# connections.net
KiCad netlist of a schematic drawn in EAGLE
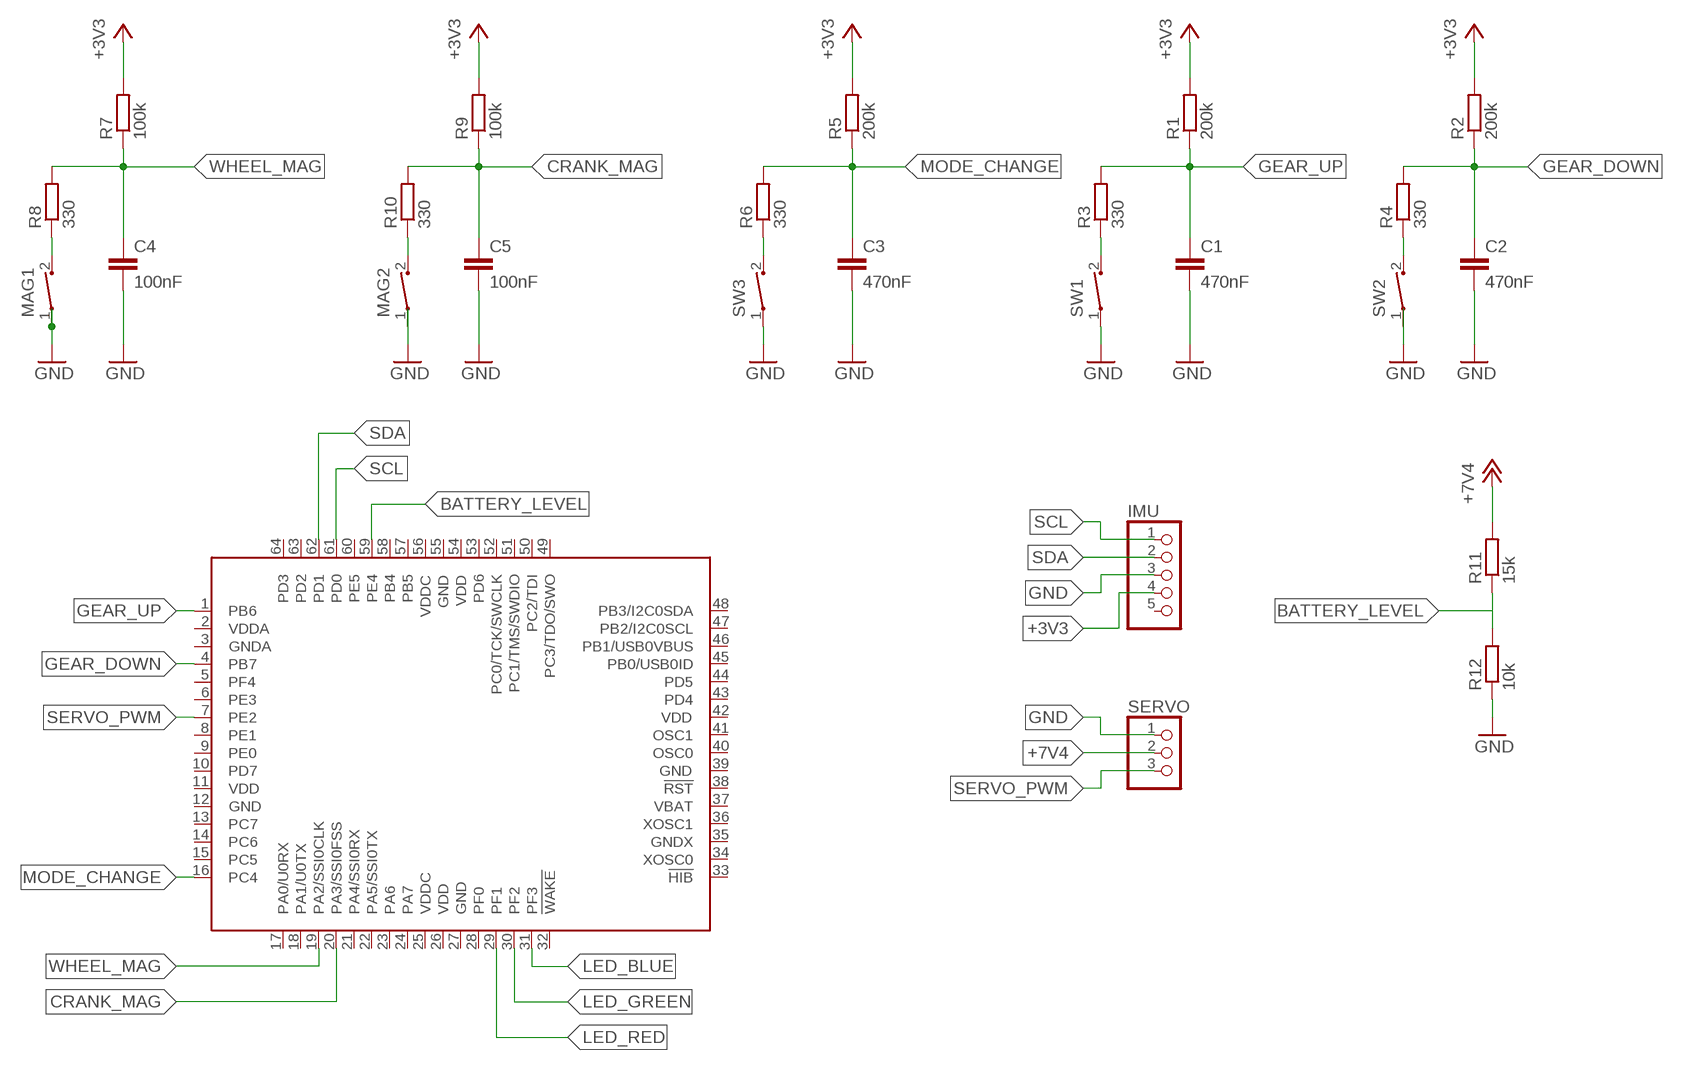
[diagram p0: schematic, sheet 1]

(export (version "E")
  (design (tool "Eeschema 10.0.6"))
  (components
    (comp (ref "C1")
      (value "470nF")
      (footprint "eagle-import:C2.5-3")
      (libsource (lib "eagle-import") (part "C2,5-3"))
    )
    (comp (ref "C2")
      (value "470nF")
      (footprint "eagle-import:C2.5-3")
      (libsource (lib "eagle-import") (part "C2,5-3"))
    )
    (comp (ref "C3")
      (value "470nF")
      (footprint "eagle-import:C2.5-3")
      (libsource (lib "eagle-import") (part "C2,5-3"))
    )
    (comp (ref "C4")
      (value "100nF")
      (footprint "eagle-import:C2.5-3")
      (libsource (lib "eagle-import") (part "C2,5-3"))
    )
    (comp (ref "C5")
      (value "100nF")
      (footprint "eagle-import:C2.5-3")
      (libsource (lib "eagle-import") (part "C2,5-3"))
    )
    (comp (ref "IC1")
      (value "TM4C123[7,G]XXPM")
      (footprint "eagle-import:PM_S-PQFP-G64")
      (libsource (lib "eagle-import") (part "TM4C123[7,G]XXPM"))
    )
    (comp (ref "IMU")
      (value "PINHD-1X5")
      (footprint "eagle-import:1X05")
      (libsource (lib "eagle-import") (part "PINHD-1X5"))
    )
    (comp (ref "MAG1")
      (value "CT10-XXXX-A2")
      (footprint "eagle-import:CT10-XXXX-A2")
      (libsource (lib "eagle-import") (part "CT10-XXXX-A2"))
    )
    (comp (ref "MAG2")
      (value "CT10-XXXX-A2")
      (footprint "eagle-import:CT10-XXXX-A2")
      (libsource (lib "eagle-import") (part "CT10-XXXX-A2"))
    )
    (comp (ref "R1")
      (value "200k")
      (footprint "eagle-import:0204_5")
      (libsource (lib "eagle-import") (part "R-EU_0204/5"))
    )
    (comp (ref "R2")
      (value "200k")
      (footprint "eagle-import:0204_5")
      (libsource (lib "eagle-import") (part "R-EU_0204/5"))
    )
    (comp (ref "R3")
      (value "330")
      (footprint "eagle-import:0204_5")
      (libsource (lib "eagle-import") (part "R-EU_0204/5"))
    )
    (comp (ref "R4")
      (value "330")
      (footprint "eagle-import:0204_5")
      (libsource (lib "eagle-import") (part "R-EU_0204/5"))
    )
    (comp (ref "R5")
      (value "200k")
      (footprint "eagle-import:0204_5")
      (libsource (lib "eagle-import") (part "R-EU_0204/5"))
    )
    (comp (ref "R6")
      (value "330")
      (footprint "eagle-import:0204_5")
      (libsource (lib "eagle-import") (part "R-EU_0204/5"))
    )
    (comp (ref "R7")
      (value "100k")
      (footprint "eagle-import:0204_5")
      (libsource (lib "eagle-import") (part "R-EU_0204/5"))
    )
    (comp (ref "R8")
      (value "330")
      (footprint "eagle-import:0204_5")
      (libsource (lib "eagle-import") (part "R-EU_0204/5"))
    )
    (comp (ref "R9")
      (value "100k")
      (footprint "eagle-import:0204_5")
      (libsource (lib "eagle-import") (part "R-EU_0204/5"))
    )
    (comp (ref "R10")
      (value "330")
      (footprint "eagle-import:0204_5")
      (libsource (lib "eagle-import") (part "R-EU_0204/5"))
    )
    (comp (ref "R11")
      (value "15k")
      (footprint "eagle-import:0204_5")
      (libsource (lib "eagle-import") (part "R-EU_0204/5"))
    )
    (comp (ref "R12")
      (value "10k")
      (footprint "eagle-import:0204_5")
      (libsource (lib "eagle-import") (part "R-EU_0204/5"))
    )
    (comp (ref "SERVO")
      (value "PINHD-1X3")
      (footprint "eagle-import:1X03")
      (libsource (lib "eagle-import") (part "PINHD-1X3"))
    )
    (comp (ref "SW1")
      (value "CT10-XXXX-A2")
      (footprint "eagle-import:CT10-XXXX-A2")
      (libsource (lib "eagle-import") (part "CT10-XXXX-A2"))
    )
    (comp (ref "SW2")
      (value "CT10-XXXX-A2")
      (footprint "eagle-import:CT10-XXXX-A2")
      (libsource (lib "eagle-import") (part "CT10-XXXX-A2"))
    )
    (comp (ref "SW3")
      (value "CT10-XXXX-A2")
      (footprint "eagle-import:CT10-XXXX-A2")
      (libsource (lib "eagle-import") (part "CT10-XXXX-A2"))
    )
  )
  (nets
    (net (code "1") (name "+3V3") (class "Default")
      (node (ref "IMU") (pin "4") (pinfunction "4_4") (pintype "passive"))
      (node (ref "R1") (pin "2") (pinfunction "2_2") (pintype "passive"))
      (node (ref "R2") (pin "2") (pinfunction "2_2") (pintype "passive"))
      (node (ref "R5") (pin "2") (pinfunction "2_2") (pintype "passive"))
      (node (ref "R7") (pin "2") (pinfunction "2_2") (pintype "passive"))
      (node (ref "R9") (pin "2") (pinfunction "2_2") (pintype "passive"))
    )
    (net (code "2") (name "+7V4") (class "Default")
      (node (ref "R11") (pin "2") (pinfunction "2_2") (pintype "passive"))
      (node (ref "SERVO") (pin "2") (pinfunction "2_2") (pintype "passive"))
    )
    (net (code "3") (name "BATTERY_LEVEL") (class "Default")
      (node (ref "IC1") (pin "59") (pinfunction "PE4_59") (pintype "bidirectional"))
      (node (ref "R11") (pin "1") (pinfunction "1_1") (pintype "passive"))
      (node (ref "R12") (pin "2") (pinfunction "2_2") (pintype "passive"))
    )
    (net (code "4") (name "CRANK_MAG") (class "Default")
      (node (ref "C5") (pin "1") (pinfunction "1_1") (pintype "passive"))
      (node (ref "IC1") (pin "20") (pinfunction "PA3/SSI0FSS_20") (pintype "bidirectional"))
      (node (ref "R10") (pin "2") (pinfunction "2_2") (pintype "passive"))
      (node (ref "R9") (pin "1") (pinfunction "1_1") (pintype "passive"))
    )
    (net (code "5") (name "GEAR_DOWN") (class "Default")
      (node (ref "C2") (pin "1") (pinfunction "1_1") (pintype "passive"))
      (node (ref "IC1") (pin "4") (pinfunction "PB7_4") (pintype "bidirectional"))
      (node (ref "R2") (pin "1") (pinfunction "1_1") (pintype "passive"))
      (node (ref "R4") (pin "2") (pinfunction "2_2") (pintype "passive"))
    )
    (net (code "6") (name "GEAR_UP") (class "Default")
      (node (ref "C1") (pin "1") (pinfunction "1_1") (pintype "passive"))
      (node (ref "IC1") (pin "1") (pinfunction "PB6_1") (pintype "bidirectional"))
      (node (ref "R1") (pin "1") (pinfunction "1_1") (pintype "passive"))
      (node (ref "R3") (pin "2") (pinfunction "2_2") (pintype "passive"))
    )
    (net (code "7") (name "GND") (class "Default")
      (node (ref "C1") (pin "2") (pinfunction "2_2") (pintype "passive"))
      (node (ref "C2") (pin "2") (pinfunction "2_2") (pintype "passive"))
      (node (ref "C3") (pin "2") (pinfunction "2_2") (pintype "passive"))
      (node (ref "C4") (pin "2") (pinfunction "2_2") (pintype "passive"))
      (node (ref "C5") (pin "2") (pinfunction "2_2") (pintype "passive"))
      (node (ref "IMU") (pin "3") (pinfunction "3_3") (pintype "passive"))
      (node (ref "MAG1") (pin "1") (pinfunction "1_1") (pintype "passive"))
      (node (ref "R12") (pin "1") (pinfunction "1_1") (pintype "passive"))
      (node (ref "SERVO") (pin "1") (pinfunction "1_1") (pintype "passive"))
      (node (ref "SW1") (pin "1") (pinfunction "1_1") (pintype "passive"))
      (node (ref "SW3") (pin "1") (pinfunction "1_1") (pintype "passive"))
    )
    (net (code "8") (name "LED_BLUE") (class "Default")
      (node (ref "IC1") (pin "31") (pinfunction "PF3_31") (pintype "bidirectional"))
    )
    (net (code "9") (name "LED_GREEN") (class "Default")
      (node (ref "IC1") (pin "30") (pinfunction "PF2_30") (pintype "bidirectional"))
    )
    (net (code "10") (name "LED_RED") (class "Default")
      (node (ref "IC1") (pin "29") (pinfunction "PF1_29") (pintype "bidirectional"))
    )
    (net (code "11") (name "MODE_CHANGE") (class "Default")
      (node (ref "C3") (pin "1") (pinfunction "1_1") (pintype "passive"))
      (node (ref "IC1") (pin "16") (pinfunction "PC4_16") (pintype "bidirectional"))
      (node (ref "R5") (pin "1") (pinfunction "1_1") (pintype "passive"))
      (node (ref "R6") (pin "2") (pinfunction "2_2") (pintype "passive"))
    )
    (net (code "12") (name "Net-(MAG1-Pad2)") (class "Default")
      (node (ref "MAG1") (pin "2") (pinfunction "2_2") (pintype "passive"))
      (node (ref "R8") (pin "1") (pinfunction "1_1") (pintype "passive"))
    )
    (net (code "13") (name "Net-(MAG2-Pad2)") (class "Default")
      (node (ref "MAG2") (pin "2") (pinfunction "2_2") (pintype "passive"))
      (node (ref "R10") (pin "1") (pinfunction "1_1") (pintype "passive"))
    )
    (net (code "14") (name "Net-(R3-Pad1)") (class "Default")
      (node (ref "R3") (pin "1") (pinfunction "1_1") (pintype "passive"))
      (node (ref "SW1") (pin "2") (pinfunction "2_2") (pintype "passive"))
    )
    (net (code "15") (name "Net-(R4-Pad1)") (class "Default")
      (node (ref "R4") (pin "1") (pinfunction "1_1") (pintype "passive"))
      (node (ref "SW2") (pin "2") (pinfunction "2_2") (pintype "passive"))
    )
    (net (code "16") (name "Net-(R6-Pad1)") (class "Default")
      (node (ref "R6") (pin "1") (pinfunction "1_1") (pintype "passive"))
      (node (ref "SW3") (pin "2") (pinfunction "2_2") (pintype "passive"))
    )
    (net (code "17") (name "SCL") (class "Default")
      (node (ref "IC1") (pin "61") (pinfunction "PD0_61") (pintype "bidirectional"))
      (node (ref "IMU") (pin "1") (pinfunction "1_1") (pintype "passive"))
    )
    (net (code "18") (name "SDA") (class "Default")
      (node (ref "IC1") (pin "62") (pinfunction "PD1_62") (pintype "bidirectional"))
      (node (ref "IMU") (pin "2") (pinfunction "2_2") (pintype "passive"))
    )
    (net (code "19") (name "SERVO_PWM") (class "Default")
      (node (ref "IC1") (pin "7") (pinfunction "PE2_7") (pintype "bidirectional"))
      (node (ref "SERVO") (pin "3") (pinfunction "3_3") (pintype "passive"))
    )
    (net (code "20") (name "WHEEL_MAG") (class "Default")
      (node (ref "C4") (pin "1") (pinfunction "1_1") (pintype "passive"))
      (node (ref "IC1") (pin "19") (pinfunction "PA2/SSI0CLK_19") (pintype "bidirectional"))
      (node (ref "R7") (pin "1") (pinfunction "1_1") (pintype "passive"))
      (node (ref "R8") (pin "2") (pinfunction "2_2") (pintype "passive"))
    )
    (net (code "21") (name "unconnected-(IC1-GND-Pad12)") (class "Default")
      (node (ref "IC1") (pin "12") (pinfunction "GND_12") (pintype "bidirectional"))
    )
    (net (code "22") (name "unconnected-(IC1-GND-Pad27)") (class "Default")
      (node (ref "IC1") (pin "27") (pinfunction "GND_27") (pintype "bidirectional"))
    )
    (net (code "23") (name "unconnected-(IC1-GND-Pad39)") (class "Default")
      (node (ref "IC1") (pin "39") (pinfunction "GND_39") (pintype "bidirectional"))
    )
    (net (code "24") (name "unconnected-(IC1-GND-Pad55)") (class "Default")
      (node (ref "IC1") (pin "55") (pinfunction "GND_55") (pintype "bidirectional"))
    )
    (net (code "25") (name "unconnected-(IC1-GNDA-Pad3)") (class "Default")
      (node (ref "IC1") (pin "3") (pinfunction "GNDA_3") (pintype "bidirectional"))
    )
    (net (code "26") (name "unconnected-(IC1-GNDX-Pad35)") (class "Default")
      (node (ref "IC1") (pin "35") (pinfunction "GNDX_35") (pintype "bidirectional"))
    )
    (net (code "27") (name "unconnected-(IC1-OSC0-Pad40)") (class "Default")
      (node (ref "IC1") (pin "40") (pinfunction "OSC0_40") (pintype "bidirectional"))
    )
    (net (code "28") (name "unconnected-(IC1-OSC1-Pad41)") (class "Default")
      (node (ref "IC1") (pin "41") (pinfunction "OSC1_41") (pintype "bidirectional"))
    )
    (net (code "29") (name "unconnected-(IC1-PA0{slash}U0RX-Pad17)") (class "Default")
      (node (ref "IC1") (pin "17") (pinfunction "PA0/U0RX_17") (pintype "bidirectional"))
    )
    (net (code "30") (name "unconnected-(IC1-PA1{slash}U0TX-Pad18)") (class "Default")
      (node (ref "IC1") (pin "18") (pinfunction "PA1/U0TX_18") (pintype "bidirectional"))
    )
    (net (code "31") (name "unconnected-(IC1-PA4{slash}SSI0RX-Pad21)") (class "Default")
      (node (ref "IC1") (pin "21") (pinfunction "PA4/SSI0RX_21") (pintype "bidirectional"))
    )
    (net (code "32") (name "unconnected-(IC1-PA5{slash}SSI0TX-Pad22)") (class "Default")
      (node (ref "IC1") (pin "22") (pinfunction "PA5/SSI0TX_22") (pintype "bidirectional"))
    )
    (net (code "33") (name "unconnected-(IC1-PA6-Pad23)") (class "Default")
      (node (ref "IC1") (pin "23") (pinfunction "PA6_23") (pintype "bidirectional"))
    )
    (net (code "34") (name "unconnected-(IC1-PA7-Pad24)") (class "Default")
      (node (ref "IC1") (pin "24") (pinfunction "PA7_24") (pintype "bidirectional"))
    )
    (net (code "35") (name "unconnected-(IC1-PB0{slash}USB0ID-Pad45)") (class "Default")
      (node (ref "IC1") (pin "45") (pinfunction "PB0/USB0ID_45") (pintype "bidirectional"))
    )
    (net (code "36") (name "unconnected-(IC1-PB1{slash}USB0VBUS-Pad46)") (class "Default")
      (node (ref "IC1") (pin "46") (pinfunction "PB1/USB0VBUS_46") (pintype "bidirectional"))
    )
    (net (code "37") (name "unconnected-(IC1-PB2{slash}I2C0SCL-Pad47)") (class "Default")
      (node (ref "IC1") (pin "47") (pinfunction "PB2/I2C0SCL_47") (pintype "bidirectional"))
    )
    (net (code "38") (name "unconnected-(IC1-PB3{slash}I2C0SDA-Pad48)") (class "Default")
      (node (ref "IC1") (pin "48") (pinfunction "PB3/I2C0SDA_48") (pintype "bidirectional"))
    )
    (net (code "39") (name "unconnected-(IC1-PB4-Pad58)") (class "Default")
      (node (ref "IC1") (pin "58") (pinfunction "PB4_58") (pintype "bidirectional"))
    )
    (net (code "40") (name "unconnected-(IC1-PB5-Pad57)") (class "Default")
      (node (ref "IC1") (pin "57") (pinfunction "PB5_57") (pintype "bidirectional"))
    )
    (net (code "41") (name "unconnected-(IC1-PC0{slash}TCK{slash}SWCLK-Pad52)") (class "Default")
      (node (ref "IC1") (pin "52") (pinfunction "PC0/TCK/SWCLK_52") (pintype "bidirectional"))
    )
    (net (code "42") (name "unconnected-(IC1-PC1{slash}TMS{slash}SWDIO-Pad51)") (class "Default")
      (node (ref "IC1") (pin "51") (pinfunction "PC1/TMS/SWDIO_51") (pintype "bidirectional"))
    )
    (net (code "43") (name "unconnected-(IC1-PC2{slash}TDI-Pad50)") (class "Default")
      (node (ref "IC1") (pin "50") (pinfunction "PC2/TDI_50") (pintype "bidirectional"))
    )
    (net (code "44") (name "unconnected-(IC1-PC3{slash}TDO{slash}SWO-Pad49)") (class "Default")
      (node (ref "IC1") (pin "49") (pinfunction "PC3/TDO/SWO_49") (pintype "bidirectional"))
    )
    (net (code "45") (name "unconnected-(IC1-PC5-Pad15)") (class "Default")
      (node (ref "IC1") (pin "15") (pinfunction "PC5_15") (pintype "bidirectional"))
    )
    (net (code "46") (name "unconnected-(IC1-PC6-Pad14)") (class "Default")
      (node (ref "IC1") (pin "14") (pinfunction "PC6_14") (pintype "bidirectional"))
    )
    (net (code "47") (name "unconnected-(IC1-PC7-Pad13)") (class "Default")
      (node (ref "IC1") (pin "13") (pinfunction "PC7_13") (pintype "bidirectional"))
    )
    (net (code "48") (name "unconnected-(IC1-PD2-Pad63)") (class "Default")
      (node (ref "IC1") (pin "63") (pinfunction "PD2_63") (pintype "bidirectional"))
    )
    (net (code "49") (name "unconnected-(IC1-PD3-Pad64)") (class "Default")
      (node (ref "IC1") (pin "64") (pinfunction "PD3_64") (pintype "bidirectional"))
    )
    (net (code "50") (name "unconnected-(IC1-PD4-Pad43)") (class "Default")
      (node (ref "IC1") (pin "43") (pinfunction "PD4_43") (pintype "bidirectional"))
    )
    (net (code "51") (name "unconnected-(IC1-PD5-Pad44)") (class "Default")
      (node (ref "IC1") (pin "44") (pinfunction "PD5_44") (pintype "bidirectional"))
    )
    (net (code "52") (name "unconnected-(IC1-PD6-Pad53)") (class "Default")
      (node (ref "IC1") (pin "53") (pinfunction "PD6_53") (pintype "bidirectional"))
    )
    (net (code "53") (name "unconnected-(IC1-PD7-Pad10)") (class "Default")
      (node (ref "IC1") (pin "10") (pinfunction "PD7_10") (pintype "bidirectional"))
    )
    (net (code "54") (name "unconnected-(IC1-PE0-Pad9)") (class "Default")
      (node (ref "IC1") (pin "9") (pinfunction "PE0_9") (pintype "bidirectional"))
    )
    (net (code "55") (name "unconnected-(IC1-PE1-Pad8)") (class "Default")
      (node (ref "IC1") (pin "8") (pinfunction "PE1_8") (pintype "bidirectional"))
    )
    (net (code "56") (name "unconnected-(IC1-PE3-Pad6)") (class "Default")
      (node (ref "IC1") (pin "6") (pinfunction "PE3_6") (pintype "bidirectional"))
    )
    (net (code "57") (name "unconnected-(IC1-PE5-Pad60)") (class "Default")
      (node (ref "IC1") (pin "60") (pinfunction "PE5_60") (pintype "bidirectional"))
    )
    (net (code "58") (name "unconnected-(IC1-PF0-Pad28)") (class "Default")
      (node (ref "IC1") (pin "28") (pinfunction "PF0_28") (pintype "bidirectional"))
    )
    (net (code "59") (name "unconnected-(IC1-PF4-Pad5)") (class "Default")
      (node (ref "IC1") (pin "5") (pinfunction "PF4_5") (pintype "bidirectional"))
    )
    (net (code "60") (name "unconnected-(IC1-VBAT-Pad37)") (class "Default")
      (node (ref "IC1") (pin "37") (pinfunction "VBAT_37") (pintype "bidirectional"))
    )
    (net (code "61") (name "unconnected-(IC1-VDD-Pad11)") (class "Default")
      (node (ref "IC1") (pin "11") (pinfunction "VDD_11") (pintype "bidirectional"))
    )
    (net (code "62") (name "unconnected-(IC1-VDD-Pad26)") (class "Default")
      (node (ref "IC1") (pin "26") (pinfunction "VDD_26") (pintype "bidirectional"))
    )
    (net (code "63") (name "unconnected-(IC1-VDD-Pad42)") (class "Default")
      (node (ref "IC1") (pin "42") (pinfunction "VDD_42") (pintype "bidirectional"))
    )
    (net (code "64") (name "unconnected-(IC1-VDD-Pad54)") (class "Default")
      (node (ref "IC1") (pin "54") (pinfunction "VDD_54") (pintype "bidirectional"))
    )
    (net (code "65") (name "unconnected-(IC1-VDDA-Pad2)") (class "Default")
      (node (ref "IC1") (pin "2") (pinfunction "VDDA_2") (pintype "bidirectional"))
    )
    (net (code "66") (name "unconnected-(IC1-VDDC-Pad25)") (class "Default")
      (node (ref "IC1") (pin "25") (pinfunction "VDDC_25") (pintype "bidirectional"))
    )
    (net (code "67") (name "unconnected-(IC1-VDDC-Pad56)") (class "Default")
      (node (ref "IC1") (pin "56") (pinfunction "VDDC_56") (pintype "bidirectional"))
    )
    (net (code "68") (name "unconnected-(IC1-XOSC0-Pad34)") (class "Default")
      (node (ref "IC1") (pin "34") (pinfunction "XOSC0_34") (pintype "bidirectional"))
    )
    (net (code "69") (name "unconnected-(IC1-XOSC1-Pad36)") (class "Default")
      (node (ref "IC1") (pin "36") (pinfunction "XOSC1_36") (pintype "bidirectional"))
    )
    (net (code "70") (name "unconnected-(IC1-~{HIB}-Pad33)") (class "Default")
      (node (ref "IC1") (pin "33") (pinfunction "~{HIB}_33") (pintype "bidirectional"))
    )
    (net (code "71") (name "unconnected-(IC1-~{RST}-Pad38)") (class "Default")
      (node (ref "IC1") (pin "38") (pinfunction "~{RST}_38") (pintype "bidirectional"))
    )
    (net (code "72") (name "unconnected-(IC1-~{WAKE}-Pad32)") (class "Default")
      (node (ref "IC1") (pin "32") (pinfunction "~{WAKE}_32") (pintype "bidirectional"))
    )
    (net (code "73") (name "unconnected-(IMU-Pad5)") (class "Default")
      (node (ref "IMU") (pin "5") (pinfunction "5_5") (pintype "passive"))
    )
    (net (code "74") (name "unconnected-(MAG2-Pad1)") (class "Default")
      (node (ref "MAG2") (pin "1") (pinfunction "1_1") (pintype "passive"))
    )
    (net (code "75") (name "unconnected-(SW2-Pad1)") (class "Default")
      (node (ref "SW2") (pin "1") (pinfunction "1_1") (pintype "passive"))
    )
  )
)
